# contact.net
KiCad netlist of a schematic drawn in EAGLE
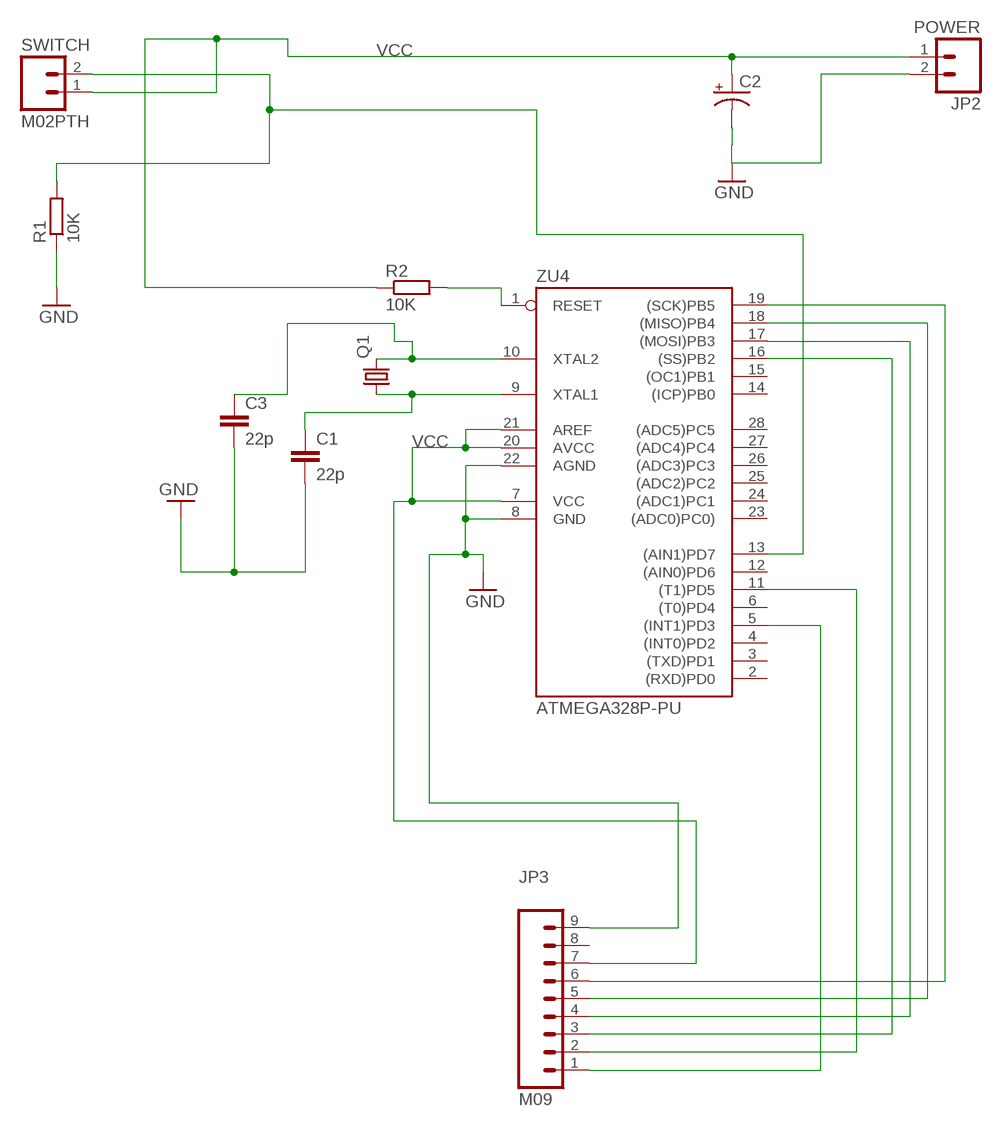
[diagram p0: schematic, sheet 1]

(export (version "E")
  (design (tool "Eeschema 10.0.6"))
  (components
    (comp (ref "C1")
      (value "22p")
      (footprint "eagle-import:C050-025X075")
      (libsource (lib "eagle-import") (part "C-EU050-025X075"))
    )
    (comp (ref "C2")
      (value "CAP_POLPTH1")
      (footprint "eagle-import:CPOL-RADIAL-100UF-25V")
      (libsource (lib "eagle-import") (part "CAP_POLPTH1"))
    )
    (comp (ref "C3")
      (value "22p")
      (footprint "eagle-import:C050-025X075")
      (libsource (lib "eagle-import") (part "C-EU050-025X075"))
    )
    (comp (ref "JP2")
      (value "POWER")
      (footprint "eagle-import:1X02")
      (libsource (lib "eagle-import") (part "M02PTH"))
    )
    (comp (ref "JP3")
      (value "M09")
      (footprint "eagle-import:1X09")
      (libsource (lib "eagle-import") (part "M09"))
    )
    (comp (ref "Q1")
      (value "CRYSTALHC49S")
      (footprint "eagle-import:HC49_S")
      (libsource (lib "eagle-import") (part "CRYSTALHC49S"))
    )
    (comp (ref "R1")
      (value "10K")
      (footprint "eagle-import:0207_7")
      (libsource (lib "eagle-import") (part "R-EU_0207/7"))
    )
    (comp (ref "R2")
      (value "10K")
      (footprint "eagle-import:0207_7")
      (libsource (lib "eagle-import") (part "R-EU_0207/7"))
    )
    (comp (ref "SWITCH")
      (value "M02PTH")
      (footprint "eagle-import:1X02")
      (libsource (lib "eagle-import") (part "M02PTH"))
    )
    (comp (ref "ZU4")
      (value "ATMEGA328P-PU")
      (footprint "eagle-import:DIL28-3")
      (libsource (lib "eagle-import") (part "ATMEGA328P-PU"))
    )
  )
  (nets
    (net (code "1") (name "/VCC") (class "Default")
      (node (ref "C2") (pin "1") (pinfunction "+_1") (pintype "passive"))
      (node (ref "JP2") (pin "1") (pinfunction "1_1") (pintype "passive"))
      (node (ref "JP3") (pin "7") (pinfunction "7_7") (pintype "passive"))
      (node (ref "R2") (pin "1") (pinfunction "1_1") (pintype "passive"))
      (node (ref "SWITCH") (pin "1") (pinfunction "1_1") (pintype "passive"))
      (node (ref "ZU4") (pin "20") (pinfunction "AVCC_20") (pintype "power_in"))
      (node (ref "ZU4") (pin "21") (pinfunction "AREF_21") (pintype "passive"))
      (node (ref "ZU4") (pin "7") (pinfunction "VCC_7") (pintype "power_in"))
    )
    (net (code "2") (name "GND") (class "Default")
      (node (ref "C1") (pin "2") (pinfunction "2_2") (pintype "passive"))
      (node (ref "C2") (pin "2") (pinfunction "-_2") (pintype "passive"))
      (node (ref "C3") (pin "2") (pinfunction "2_2") (pintype "passive"))
      (node (ref "JP2") (pin "2") (pinfunction "2_2") (pintype "passive"))
      (node (ref "JP3") (pin "9") (pinfunction "9_9") (pintype "passive"))
      (node (ref "R1") (pin "1") (pinfunction "1_1") (pintype "passive"))
      (node (ref "ZU4") (pin "22") (pinfunction "AGND_22") (pintype "power_in"))
      (node (ref "ZU4") (pin "8") (pinfunction "GND_8") (pintype "power_in"))
    )
    (net (code "3") (name "Net-(ZU4-(AIN1)PD7)") (class "Default")
      (node (ref "R1") (pin "2") (pinfunction "2_2") (pintype "passive"))
      (node (ref "SWITCH") (pin "2") (pinfunction "2_2") (pintype "passive"))
      (node (ref "ZU4") (pin "13") (pinfunction "(AIN1)PD7_13") (pintype "bidirectional"))
    )
    (net (code "4") (name "Net-(ZU4-(INT1)PD3)") (class "Default")
      (node (ref "JP3") (pin "1") (pinfunction "1_1") (pintype "passive"))
      (node (ref "ZU4") (pin "5") (pinfunction "(INT1)PD3_5") (pintype "bidirectional"))
    )
    (net (code "5") (name "Net-(ZU4-(MISO)PB4)") (class "Default")
      (node (ref "JP3") (pin "5") (pinfunction "5_5") (pintype "passive"))
      (node (ref "ZU4") (pin "18") (pinfunction "(MISO)PB4_18") (pintype "bidirectional"))
    )
    (net (code "6") (name "Net-(ZU4-(MOSI)PB3)") (class "Default")
      (node (ref "JP3") (pin "4") (pinfunction "4_4") (pintype "passive"))
      (node (ref "ZU4") (pin "17") (pinfunction "(MOSI)PB3_17") (pintype "bidirectional"))
    )
    (net (code "7") (name "Net-(ZU4-(SCK)PB5)") (class "Default")
      (node (ref "JP3") (pin "6") (pinfunction "6_6") (pintype "passive"))
      (node (ref "ZU4") (pin "19") (pinfunction "(SCK)PB5_19") (pintype "bidirectional"))
    )
    (net (code "8") (name "Net-(ZU4-(SS)PB2)") (class "Default")
      (node (ref "JP3") (pin "3") (pinfunction "3_3") (pintype "passive"))
      (node (ref "ZU4") (pin "16") (pinfunction "(SS)PB2_16") (pintype "bidirectional"))
    )
    (net (code "9") (name "Net-(ZU4-(T1)PD5)") (class "Default")
      (node (ref "JP3") (pin "2") (pinfunction "2_2") (pintype "passive"))
      (node (ref "ZU4") (pin "11") (pinfunction "(T1)PD5_11") (pintype "bidirectional"))
    )
    (net (code "10") (name "Net-(ZU4-RESET)") (class "Default")
      (node (ref "R2") (pin "2") (pinfunction "2_2") (pintype "passive"))
      (node (ref "ZU4") (pin "1") (pinfunction "RESET_1") (pintype "input"))
    )
    (net (code "11") (name "Net-(ZU4-XTAL1)") (class "Default")
      (node (ref "C1") (pin "1") (pinfunction "1_1") (pintype "passive"))
      (node (ref "Q1") (pin "1") (pinfunction "1_1") (pintype "passive"))
      (node (ref "ZU4") (pin "9") (pinfunction "XTAL1_9") (pintype "bidirectional"))
    )
    (net (code "12") (name "Net-(ZU4-XTAL2)") (class "Default")
      (node (ref "C3") (pin "1") (pinfunction "1_1") (pintype "passive"))
      (node (ref "Q1") (pin "2") (pinfunction "2_2") (pintype "passive"))
      (node (ref "ZU4") (pin "10") (pinfunction "XTAL2_10") (pintype "bidirectional"))
    )
    (net (code "13") (name "unconnected-(JP3-Pad8)") (class "Default")
      (node (ref "JP3") (pin "8") (pinfunction "8_8") (pintype "passive"))
    )
    (net (code "14") (name "unconnected-(ZU4-(ADC0)PC0)-Pad23)") (class "Default")
      (node (ref "ZU4") (pin "23") (pinfunction "(ADC0)PC0)_23") (pintype "bidirectional"))
    )
    (net (code "15") (name "unconnected-(ZU4-(ADC1)PC1-Pad24)") (class "Default")
      (node (ref "ZU4") (pin "24") (pinfunction "(ADC1)PC1_24") (pintype "bidirectional"))
    )
    (net (code "16") (name "unconnected-(ZU4-(ADC2)PC2-Pad25)") (class "Default")
      (node (ref "ZU4") (pin "25") (pinfunction "(ADC2)PC2_25") (pintype "bidirectional"))
    )
    (net (code "17") (name "unconnected-(ZU4-(ADC3)PC3-Pad26)") (class "Default")
      (node (ref "ZU4") (pin "26") (pinfunction "(ADC3)PC3_26") (pintype "bidirectional"))
    )
    (net (code "18") (name "unconnected-(ZU4-(ADC4)PC4-Pad27)") (class "Default")
      (node (ref "ZU4") (pin "27") (pinfunction "(ADC4)PC4_27") (pintype "bidirectional"))
    )
    (net (code "19") (name "unconnected-(ZU4-(ADC5)PC5-Pad28)") (class "Default")
      (node (ref "ZU4") (pin "28") (pinfunction "(ADC5)PC5_28") (pintype "bidirectional"))
    )
    (net (code "20") (name "unconnected-(ZU4-(AIN0)PD6-Pad12)") (class "Default")
      (node (ref "ZU4") (pin "12") (pinfunction "(AIN0)PD6_12") (pintype "bidirectional"))
    )
    (net (code "21") (name "unconnected-(ZU4-(ICP)PB0-Pad14)") (class "Default")
      (node (ref "ZU4") (pin "14") (pinfunction "(ICP)PB0_14") (pintype "bidirectional"))
    )
    (net (code "22") (name "unconnected-(ZU4-(INT0)PD2-Pad4)") (class "Default")
      (node (ref "ZU4") (pin "4") (pinfunction "(INT0)PD2_4") (pintype "bidirectional"))
    )
    (net (code "23") (name "unconnected-(ZU4-(OC1)PB1-Pad15)") (class "Default")
      (node (ref "ZU4") (pin "15") (pinfunction "(OC1)PB1_15") (pintype "bidirectional"))
    )
    (net (code "24") (name "unconnected-(ZU4-(RXD)PD0-Pad2)") (class "Default")
      (node (ref "ZU4") (pin "2") (pinfunction "(RXD)PD0_2") (pintype "bidirectional"))
    )
    (net (code "25") (name "unconnected-(ZU4-(T0)PD4-Pad6)") (class "Default")
      (node (ref "ZU4") (pin "6") (pinfunction "(T0)PD4_6") (pintype "bidirectional"))
    )
    (net (code "26") (name "unconnected-(ZU4-(TXD)PD1-Pad3)") (class "Default")
      (node (ref "ZU4") (pin "3") (pinfunction "(TXD)PD1_3") (pintype "bidirectional"))
    )
  )
)
